# UART.net
KiCad netlist of a schematic drawn in Altium Designer
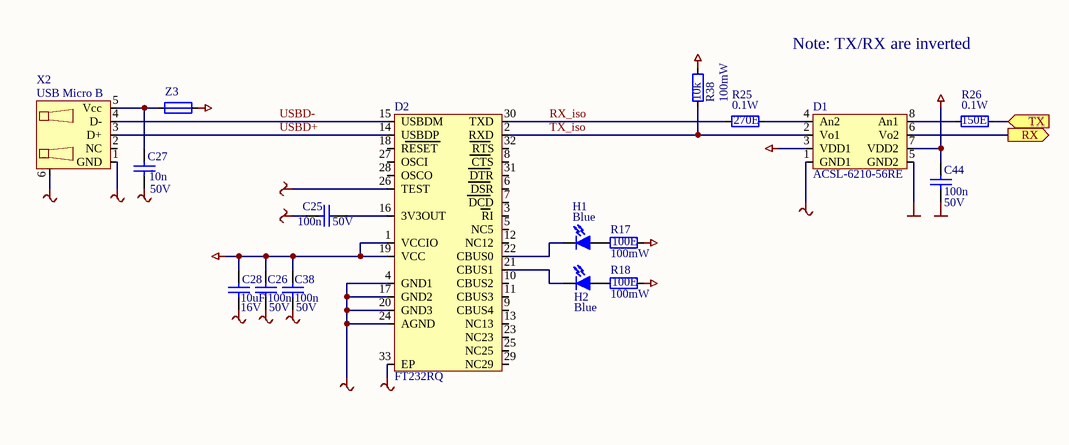
[diagram p0: UART.SCHDOC]

(export (version "E")
  (design (tool "Eeschema 10.0.6"))
  (components
    (comp (ref "C25")
      (value "C_SMD_CER_100N_50V_10%_X7R_0603")
      (footprint "SMD_0603")
      (description "SMD Capacitor")
      (fields (field (name "ALTIUM_VALUE") "100n") (field (name "VALUE2") "50V"))
      (libsource (lib "C-Capacitor") (part "C_SMD_CER_100N_50V_10%_X7R_0603"))
    )
    (comp (ref "C26")
      (value "C_SMD_CER_100N_50V_10%_X7R_0603")
      (footprint "SMD_0603")
      (description "SMD Capacitor")
      (fields (field (name "ALTIUM_VALUE") "100n") (field (name "VALUE2") "50V"))
      (libsource (lib "C-Capacitor") (part "C_SMD_CER_100N_50V_10%_X7R_0603"))
    )
    (comp (ref "C27")
      (value "C_SMD_CER_10N_50V_10%_X7R_0603")
      (footprint "SMD_0603")
      (description "SMD Capacitor")
      (fields (field (name "ALTIUM_VALUE") "10n") (field (name "VALUE2") "50V"))
      (libsource (lib "C-Capacitor") (part "C_SMD_CER_10N_50V_10%_X7R_0603"))
    )
    (comp (ref "C28")
      (value "C_SMD_CER_10U_16V_10%_X5R_0805")
      (footprint "SMD_0805")
      (description "SMD Capacitor")
      (fields (field (name "ALTIUM_VALUE") "10uF") (field (name "VALUE2") "16V"))
      (libsource (lib "C-Capacitor") (part "C_SMD_CER_10U_16V_10%_X5R_0805"))
    )
    (comp (ref "C38")
      (value "C_SMD_CER_100N_50V_10%_X7R_0603")
      (footprint "SMD_0603")
      (description "SMD Capacitor")
      (fields (field (name "ALTIUM_VALUE") "100n") (field (name "VALUE2") "50V"))
      (libsource (lib "C-Capacitor") (part "C_SMD_CER_100N_50V_10%_X7R_0603"))
    )
    (comp (ref "C44")
      (value "C_SMD_CER_100N_50V_10%_X7R_0603")
      (footprint "SMD_0603")
      (description "SMD Capacitor")
      (fields (field (name "ALTIUM_VALUE") "100n") (field (name "VALUE2") "50V"))
      (libsource (lib "C-Capacitor") (part "C_SMD_CER_100N_50V_10%_X7R_0603"))
    )
    (comp (ref "D1")
      (value "D_ACSL-6210_SO-8")
      (footprint "SMD_SOP_8")
      (description "Multi-Channel and Bi-Directional 15MBd Digital Logic Gate Optocoupler")
      (fields (field (name "TYPE") "ACSL-6210-56RE"))
      (libsource (lib "D-Digital") (part "D_ACSL-6210_SO-8"))
    )
    (comp (ref "D2")
      (value "D_FT232RQ")
      (footprint "SMD_QFN-32")
      (description "FT232r USB UART IC")
      (fields (field (name "TYPE") "FT232RQ"))
      (libsource (lib "D-Digital") (part "D_FT232RQ"))
    )
    (comp (ref "H1")
      (value "H_SMD_LED_BLUE_0603")
      (footprint "SMD_0603P")
      (description "Blue LED, 5mA")
      (fields (field (name "TYPE") "Blue"))
      (libsource (lib "H-Signaling device") (part "H_SMD_LED_BLUE_0603"))
    )
    (comp (ref "H2")
      (value "H_SMD_LED_BLUE_0603")
      (footprint "SMD_0603P")
      (description "Blue LED, 5mA")
      (fields (field (name "TYPE") "Blue"))
      (libsource (lib "H-Signaling device") (part "H_SMD_LED_BLUE_0603"))
    )
    (comp (ref "R17")
      (value "R_SMD_THINFILM_100E_0W1_1%_50PPM_0603")
      (footprint "SMD_0603")
      (description "SMD Resistor")
      (fields (field (name "ALTIUM_VALUE") "100E") (field (name "VALUE2") "100mW"))
      (libsource (lib "R-Resistor") (part "R_SMD_THINFILM_100E_0W1_1%_50PPM_0603"))
    )
    (comp (ref "R18")
      (value "R_SMD_THINFILM_100E_0W1_1%_50PPM_0603")
      (footprint "SMD_0603")
      (description "SMD Resistor")
      (fields (field (name "ALTIUM_VALUE") "100E") (field (name "VALUE2") "100mW"))
      (libsource (lib "R-Resistor") (part "R_SMD_THINFILM_100E_0W1_1%_50PPM_0603"))
    )
    (comp (ref "R25")
      (value "R_SMD_THINFILM_270E_0W1_1%_50PPM_0603")
      (footprint "SMD_0603")
      (description "SMD Resistor")
      (fields (field (name "ALTIUM_VALUE") "270E") (field (name "VALUE2") "0.1W"))
      (libsource (lib "R-Resistor") (part "R_SMD_THINFILM_270E_0W1_1%_50PPM_0603"))
    )
    (comp (ref "R26")
      (value "R_SMD_THINFILM_150E_0W1_1%_50PPM_0603")
      (footprint "SMD_0603")
      (description "SMD Resistor")
      (fields (field (name "ALTIUM_VALUE") "150E") (field (name "VALUE2") "0.1W"))
      (libsource (lib "R-Resistor") (part "R_SMD_THINFILM_150E_0W1_1%_50PPM_0603"))
    )
    (comp (ref "R38")
      (value "R_SMD_THINFILM_10K_0W1_1%_50PPM_0603")
      (footprint "SMD_0603")
      (description "SMD Resistor")
      (fields (field (name "ALTIUM_VALUE") "10k") (field (name "VALUE2") "100mW"))
      (libsource (lib "AM") (part "R_SMD_THINFILM_10K_0W1_1%_50PPM_0603"))
    )
    (comp (ref "X2")
      (value "X_SMD_USB_MICRO-B_2.0")
      (footprint "SMD_USB_MICRO_B_2.0")
      (fields (field (name "TYPE") "USB Micro B"))
      (libsource (lib "AM") (part "X_SMD_USB_MICRO-B_2.0"))
    )
    (comp (ref "Z3")
      (value "Z_SMD_FERRITE_1A5_470E@100MHZ_0603")
      (footprint "SMD_0603")
      (description "FERRITE CHIP 470 OHM 1500MA 0603")
      (libsource (lib "AM") (part "Z_SMD_FERRITE_1A5_470E@100MHZ_0603"))
    )
  )
  (nets
    (net (code "1") (name "+3.3V") (class "Default")
      (node (ref "C44") (pin "2") (pinfunction "2_2") (pintype "passive"))
      (node (ref "D1") (pin "7") (pinfunction "VDD2_7") (pintype "passive"))
    )
    (net (code "2") (name "+5Vi") (class "Default")
      (node (ref "C26") (pin "2") (pinfunction "2_2") (pintype "passive"))
      (node (ref "C28") (pin "2") (pinfunction "2_2") (pintype "passive"))
      (node (ref "C38") (pin "2") (pinfunction "2_2") (pintype "passive"))
      (node (ref "D1") (pin "3") (pinfunction "VDD1_3") (pintype "passive"))
      (node (ref "D2") (pin "1") (pinfunction "VCCIO_1") (pintype "passive"))
      (node (ref "D2") (pin "19") (pinfunction "VCC_19") (pintype "passive"))
      (node (ref "R17") (pin "2") (pinfunction "2_2") (pintype "passive"))
      (node (ref "R18") (pin "2") (pinfunction "2_2") (pintype "passive"))
      (node (ref "R38") (pin "2") (pinfunction "2_2") (pintype "passive"))
      (node (ref "Z3") (pin "2") (pinfunction "2_2") (pintype "passive"))
    )
    (net (code "3") (name "/RX") (class "Default")
      (node (ref "D1") (pin "6") (pinfunction "Vo2_6") (pintype "passive"))
    )
    (net (code "4") (name "/RX_iso") (class "Default")
      (node (ref "D2") (pin "30") (pinfunction "TXD_30") (pintype "passive"))
      (node (ref "R25") (pin "1") (pinfunction "1_1") (pintype "passive"))
    )
    (net (code "5") (name "/TX") (class "Default")
      (node (ref "R26") (pin "2") (pinfunction "2_2") (pintype "passive"))
    )
    (net (code "6") (name "/TX_iso") (class "Default")
      (node (ref "D1") (pin "2") (pinfunction "Vo1_2") (pintype "passive"))
      (node (ref "D2") (pin "2") (pinfunction "RXD_2") (pintype "passive"))
      (node (ref "R38") (pin "1") (pinfunction "1_1") (pintype "passive"))
    )
    (net (code "7") (name "/USBD+") (class "Default")
      (node (ref "D2") (pin "14") (pinfunction "USBDP_14") (pintype "passive"))
      (node (ref "X2") (pin "3") (pinfunction "D+_3") (pintype "passive"))
    )
    (net (code "8") (name "/USBD-") (class "Default")
      (node (ref "D2") (pin "15") (pinfunction "USBDM_15") (pintype "passive"))
      (node (ref "X2") (pin "4") (pinfunction "D-_4") (pintype "passive"))
    )
    (net (code "9") (name "GND") (class "Default")
      (node (ref "C44") (pin "1") (pinfunction "1_1") (pintype "passive"))
      (node (ref "D1") (pin "5") (pinfunction "GND2_5") (pintype "passive"))
    )
    (net (code "10") (name "GNDi") (class "Default")
      (node (ref "C25") (pin "1") (pinfunction "1_1") (pintype "passive"))
      (node (ref "C26") (pin "1") (pinfunction "1_1") (pintype "passive"))
      (node (ref "C27") (pin "1") (pinfunction "1_1") (pintype "passive"))
      (node (ref "C28") (pin "1") (pinfunction "1_1") (pintype "passive"))
      (node (ref "C38") (pin "1") (pinfunction "1_1") (pintype "passive"))
      (node (ref "D1") (pin "1") (pinfunction "GND1_1") (pintype "passive"))
      (node (ref "D2") (pin "17") (pinfunction "GND2_17") (pintype "passive"))
      (node (ref "D2") (pin "20") (pinfunction "GND3_20") (pintype "passive"))
      (node (ref "D2") (pin "24") (pinfunction "AGND_24") (pintype "passive"))
      (node (ref "D2") (pin "26") (pinfunction "TEST_26") (pintype "passive"))
      (node (ref "D2") (pin "33") (pinfunction "EP_33") (pintype "passive"))
      (node (ref "D2") (pin "4") (pinfunction "GND1_4") (pintype "passive"))
      (node (ref "X2") (pin "1") (pinfunction "GND_1") (pintype "passive"))
      (node (ref "X2") (pin "6") (pinfunction "Shield_6") (pintype "passive"))
    )
    (net (code "11") (name "Net-(D1-An1)") (class "Default")
      (node (ref "D1") (pin "8") (pinfunction "An1_8") (pintype "passive"))
      (node (ref "R26") (pin "1") (pinfunction "1_1") (pintype "passive"))
    )
    (net (code "12") (name "Net-(D1-An2)") (class "Default")
      (node (ref "D1") (pin "4") (pinfunction "An2_4") (pintype "passive"))
      (node (ref "R25") (pin "2") (pinfunction "2_2") (pintype "passive"))
    )
    (net (code "13") (name "Net-(D2-3V3OUT)") (class "Default")
      (node (ref "C25") (pin "2") (pinfunction "2_2") (pintype "passive"))
      (node (ref "D2") (pin "16") (pinfunction "3V3OUT_16") (pintype "passive"))
    )
    (net (code "14") (name "Net-(D2-CBUS0)") (class "Default")
      (node (ref "D2") (pin "22") (pinfunction "CBUS0_22") (pintype "passive"))
      (node (ref "H1") (pin "2") (pinfunction "2_2") (pintype "passive"))
    )
    (net (code "15") (name "Net-(D2-CBUS1)") (class "Default")
      (node (ref "D2") (pin "21") (pinfunction "CBUS1_21") (pintype "passive"))
      (node (ref "H2") (pin "2") (pinfunction "2_2") (pintype "passive"))
    )
    (net (code "16") (name "Net-(H1-Pad1)") (class "Default")
      (node (ref "H1") (pin "1") (pinfunction "1_1") (pintype "passive"))
      (node (ref "R17") (pin "1") (pinfunction "1_1") (pintype "passive"))
    )
    (net (code "17") (name "Net-(H2-Pad1)") (class "Default")
      (node (ref "H2") (pin "1") (pinfunction "1_1") (pintype "passive"))
      (node (ref "R18") (pin "1") (pinfunction "1_1") (pintype "passive"))
    )
    (net (code "18") (name "Net-(X2-Vcc)") (class "Default")
      (node (ref "C27") (pin "2") (pinfunction "2_2") (pintype "passive"))
      (node (ref "X2") (pin "5") (pinfunction "Vcc_5") (pintype "passive"))
      (node (ref "Z3") (pin "1") (pinfunction "1_1") (pintype "passive"))
    )
    (net (code "19") (name "unconnected-(D2-CBUS2-Pad10)") (class "Default")
      (node (ref "D2") (pin "10") (pinfunction "CBUS2_10") (pintype "passive"))
    )
    (net (code "20") (name "unconnected-(D2-CBUS3-Pad11)") (class "Default")
      (node (ref "D2") (pin "11") (pinfunction "CBUS3_11") (pintype "passive"))
    )
    (net (code "21") (name "unconnected-(D2-CBUS4-Pad9)") (class "Default")
      (node (ref "D2") (pin "9") (pinfunction "CBUS4_9") (pintype "passive"))
    )
    (net (code "22") (name "unconnected-(D2-CTS-Pad8)") (class "Default")
      (node (ref "D2") (pin "8") (pinfunction "CTS_8") (pintype "passive"))
    )
    (net (code "23") (name "unconnected-(D2-DCD-Pad7)") (class "Default")
      (node (ref "D2") (pin "7") (pinfunction "DCD_7") (pintype "passive"))
    )
    (net (code "24") (name "unconnected-(D2-DSR-Pad6)") (class "Default")
      (node (ref "D2") (pin "6") (pinfunction "DSR_6") (pintype "passive"))
    )
    (net (code "25") (name "unconnected-(D2-DTR-Pad31)") (class "Default")
      (node (ref "D2") (pin "31") (pinfunction "DTR_31") (pintype "passive"))
    )
    (net (code "26") (name "unconnected-(D2-NC5-Pad5)") (class "Default")
      (node (ref "D2") (pin "5") (pinfunction "NC5_5") (pintype "passive"))
    )
    (net (code "27") (name "unconnected-(D2-NC12-Pad12)") (class "Default")
      (node (ref "D2") (pin "12") (pinfunction "NC12_12") (pintype "passive"))
    )
    (net (code "28") (name "unconnected-(D2-NC13-Pad13)") (class "Default")
      (node (ref "D2") (pin "13") (pinfunction "NC13_13") (pintype "passive"))
    )
    (net (code "29") (name "unconnected-(D2-NC23-Pad23)") (class "Default")
      (node (ref "D2") (pin "23") (pinfunction "NC23_23") (pintype "passive"))
    )
    (net (code "30") (name "unconnected-(D2-NC25-Pad25)") (class "Default")
      (node (ref "D2") (pin "25") (pinfunction "NC25_25") (pintype "passive"))
    )
    (net (code "31") (name "unconnected-(D2-NC29-Pad29)") (class "Default")
      (node (ref "D2") (pin "29") (pinfunction "NC29_29") (pintype "passive"))
    )
    (net (code "32") (name "unconnected-(D2-OSCI-Pad27)") (class "Default")
      (node (ref "D2") (pin "27") (pinfunction "OSCI_27") (pintype "passive"))
    )
    (net (code "33") (name "unconnected-(D2-OSCO-Pad28)") (class "Default")
      (node (ref "D2") (pin "28") (pinfunction "OSCO_28") (pintype "passive"))
    )
    (net (code "34") (name "unconnected-(D2-RESET-Pad18)") (class "Default")
      (node (ref "D2") (pin "18") (pinfunction "RESET_18") (pintype "passive"))
    )
    (net (code "35") (name "unconnected-(D2-RI-Pad3)") (class "Default")
      (node (ref "D2") (pin "3") (pinfunction "RI_3") (pintype "passive"))
    )
    (net (code "36") (name "unconnected-(D2-RTS-Pad32)") (class "Default")
      (node (ref "D2") (pin "32") (pinfunction "RTS_32") (pintype "passive"))
    )
    (net (code "37") (name "unconnected-(X2-NC-Pad2)") (class "Default")
      (node (ref "X2") (pin "2") (pinfunction "NC_2") (pintype "passive"))
    )
  )
)
